# ginabt.net
KiCad netlist of a schematic drawn in EAGLE
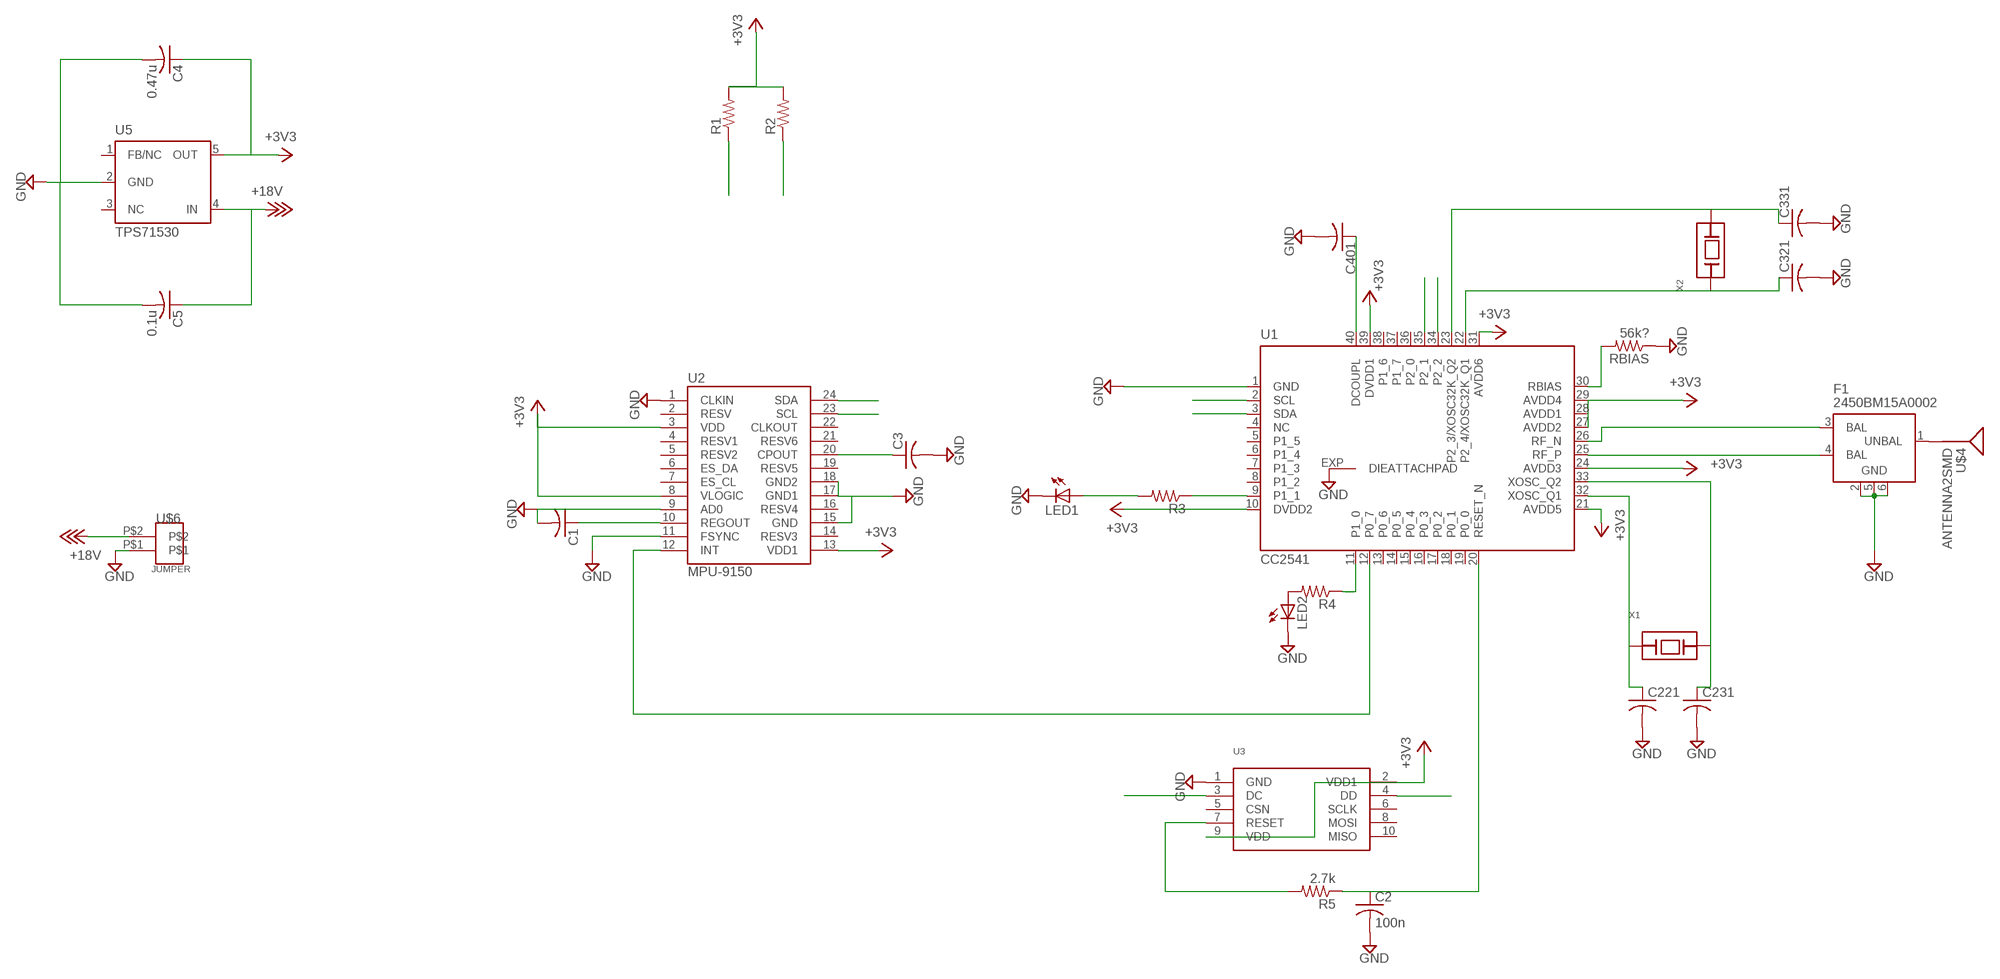
[diagram p0: schematic, sheet 1]

(export (version "E")
  (design (tool "Eeschema 10.0.6"))
  (components
    (comp (ref "C1")
      (value "C-USC0402K")
      (footprint "eagle-import:C0402K")
      (libsource (lib "eagle-import") (part "C-USC0402K"))
    )
    (comp (ref "C2")
      (value "100n")
      (footprint "eagle-import:C0402K")
      (libsource (lib "eagle-import") (part "C-USC0402K"))
    )
    (comp (ref "C3")
      (value "C-USC0402K")
      (footprint "eagle-import:C0402K")
      (libsource (lib "eagle-import") (part "C-USC0402K"))
    )
    (comp (ref "C4")
      (value "0.47u")
      (footprint "eagle-import:C0402K")
      (libsource (lib "eagle-import") (part "C-USC0402K"))
    )
    (comp (ref "C5")
      (value "0.1u")
      (footprint "eagle-import:C0402K")
      (libsource (lib "eagle-import") (part "C-USC0402K"))
    )
    (comp (ref "C221")
      (value "C-USC0402K")
      (footprint "eagle-import:C0402K")
      (libsource (lib "eagle-import") (part "C-USC0402K"))
    )
    (comp (ref "C231")
      (value "C-USC0402K")
      (footprint "eagle-import:C0402K")
      (libsource (lib "eagle-import") (part "C-USC0402K"))
    )
    (comp (ref "C321")
      (value "C-USC0402K")
      (footprint "eagle-import:C0402K")
      (libsource (lib "eagle-import") (part "C-USC0402K"))
    )
    (comp (ref "C331")
      (value "C-USC0402K")
      (footprint "eagle-import:C0402K")
      (libsource (lib "eagle-import") (part "C-USC0402K"))
    )
    (comp (ref "C401")
      (value "C-USC0402K")
      (footprint "eagle-import:C0402K")
      (libsource (lib "eagle-import") (part "C-USC0402K"))
    )
    (comp (ref "F1")
      (value "2450BM15A0002")
      (footprint "eagle-import:2450BM15A0002")
      (libsource (lib "eagle-import") (part "2450BM15A0002"))
    )
    (comp (ref "LED1")
      (value "LED")
      (footprint "eagle-import:SMARTLED-TTW")
      (libsource (lib "eagle-import") (part "LED"))
    )
    (comp (ref "LED2")
      (value "LED")
      (footprint "eagle-import:SMARTLED-TTW")
      (libsource (lib "eagle-import") (part "LED"))
    )
    (comp (ref "R1")
      (value "R-US_R0402")
      (footprint "eagle-import:R0402")
      (libsource (lib "eagle-import") (part "R-US_R0402"))
    )
    (comp (ref "R2")
      (value "R-US_R0402")
      (footprint "eagle-import:R0402")
      (libsource (lib "eagle-import") (part "R-US_R0402"))
    )
    (comp (ref "R3")
      (value "R-US_R0402")
      (footprint "eagle-import:R0402")
      (libsource (lib "eagle-import") (part "R-US_R0402"))
    )
    (comp (ref "R4")
      (value "R-US_R0402")
      (footprint "eagle-import:R0402")
      (libsource (lib "eagle-import") (part "R-US_R0402"))
    )
    (comp (ref "R5")
      (value "2.7k")
      (footprint "eagle-import:R0402")
      (libsource (lib "eagle-import") (part "R-US_R0402"))
    )
    (comp (ref "RBIAS")
      (value "56k?")
      (footprint "eagle-import:R0402")
      (libsource (lib "eagle-import") (part "R-US_R0402"))
    )
    (comp (ref "U$4")
      (value "ANTENNA2SMD")
      (footprint "eagle-import:ANTENNA-CHIP2")
      (libsource (lib "eagle-import") (part "ANTENNA2SMD"))
    )
    (comp (ref "U$6")
      (value "JUMPER")
      (footprint "eagle-import:JUMPER_1X2_80MIL")
      (libsource (lib "eagle-import") (part "JUMPER"))
    )
    (comp (ref "U1")
      (value "CC2541")
      (footprint "eagle-import:RHA_S-PVQFN-N40")
      (libsource (lib "eagle-import") (part "CC2541"))
    )
    (comp (ref "U2")
      (value "MPU-9150")
      (footprint "eagle-import:LGA-24")
      (libsource (lib "eagle-import") (part "MPU-9150"))
    )
    (comp (ref "U3")
      (value "CCDEBUGGER")
      (footprint "eagle-import:SMD-050-HEADER-2X5")
      (libsource (lib "eagle-import") (part "CCDEBUGGER"))
    )
    (comp (ref "U5")
      (value "TPS71530")
      (footprint "eagle-import:DCK_R-PDSO-G5")
      (libsource (lib "eagle-import") (part "TPS71530"))
    )
    (comp (ref "X1")
      (value "XTALABS07")
      (footprint "eagle-import:ABS07")
      (libsource (lib "eagle-import") (part "XTALABS07"))
    )
    (comp (ref "X2")
      (value "XTALCX3225SA")
      (footprint "eagle-import:CX3225SA")
      (libsource (lib "eagle-import") (part "XTALCX3225SA"))
    )
  )
  (nets
    (net (code "1") (name "+3V3") (class "Default")
      (node (ref "C4") (pin "1") (pinfunction "1_1") (pintype "passive"))
      (node (ref "R1") (pin "2") (pinfunction "2_2") (pintype "passive"))
      (node (ref "R2") (pin "2") (pinfunction "2_2") (pintype "passive"))
      (node (ref "U1") (pin "10") (pinfunction "DVDD2_10") (pintype "power_in"))
      (node (ref "U1") (pin "21") (pinfunction "AVDD5_21") (pintype "power_in"))
      (node (ref "U1") (pin "24") (pinfunction "AVDD3_24") (pintype "power_in"))
      (node (ref "U1") (pin "27") (pinfunction "AVDD2_27") (pintype "power_in"))
      (node (ref "U1") (pin "28") (pinfunction "AVDD1_28") (pintype "power_in"))
      (node (ref "U1") (pin "29") (pinfunction "AVDD4_29") (pintype "power_in"))
      (node (ref "U1") (pin "31") (pinfunction "AVDD6_31") (pintype "power_in"))
      (node (ref "U1") (pin "39") (pinfunction "DVDD1_39") (pintype "power_in"))
      (node (ref "U2") (pin "13") (pinfunction "VDD1_13") (pintype "bidirectional"))
      (node (ref "U2") (pin "3") (pinfunction "VDD_3") (pintype "power_in"))
      (node (ref "U2") (pin "8") (pinfunction "VLOGIC_8") (pintype "bidirectional"))
      (node (ref "U3") (pin "2") (pinfunction "VDD1_2") (pintype "bidirectional"))
      (node (ref "U3") (pin "9") (pinfunction "VDD_9") (pintype "bidirectional"))
      (node (ref "U5") (pin "5") (pinfunction "OUT_5") (pintype "passive"))
    )
    (net (code "2") (name "+18V") (class "Default")
      (node (ref "C5") (pin "1") (pinfunction "1_1") (pintype "passive"))
      (node (ref "U$6") (pin "P$2") (pinfunction "P$2_P$2") (pintype "bidirectional"))
      (node (ref "U5") (pin "4") (pinfunction "IN_4") (pintype "passive"))
    )
    (net (code "3") (name "/DC") (class "Default")
      (node (ref "U1") (pin "34") (pinfunction "P2_2_34") (pintype "bidirectional"))
      (node (ref "U3") (pin "3") (pinfunction "DC_3") (pintype "bidirectional"))
    )
    (net (code "4") (name "/DD") (class "Default")
      (node (ref "U1") (pin "35") (pinfunction "P2_1_35") (pintype "bidirectional"))
      (node (ref "U3") (pin "4") (pinfunction "DD_4") (pintype "bidirectional"))
    )
    (net (code "5") (name "/NC") (class "Default")
      (node (ref "U5") (pin "3") (pinfunction "NC_3") (pintype "power_in"))
    )
    (net (code "6") (name "/SCL") (class "Default")
      (node (ref "R1") (pin "1") (pinfunction "1_1") (pintype "passive"))
      (node (ref "U1") (pin "2") (pinfunction "SCL_2") (pintype "bidirectional"))
      (node (ref "U2") (pin "23") (pinfunction "SCL_23") (pintype "bidirectional"))
    )
    (net (code "7") (name "/SDA") (class "Default")
      (node (ref "R2") (pin "1") (pinfunction "1_1") (pintype "passive"))
      (node (ref "U1") (pin "3") (pinfunction "SDA_3") (pintype "bidirectional"))
      (node (ref "U2") (pin "24") (pinfunction "SDA_24") (pintype "bidirectional"))
    )
    (net (code "8") (name "GND") (class "Default")
      (node (ref "C1") (pin "2") (pinfunction "2_2") (pintype "passive"))
      (node (ref "C2") (pin "2") (pinfunction "2_2") (pintype "passive"))
      (node (ref "C221") (pin "2") (pinfunction "2_2") (pintype "passive"))
      (node (ref "C231") (pin "2") (pinfunction "2_2") (pintype "passive"))
      (node (ref "C3") (pin "2") (pinfunction "2_2") (pintype "passive"))
      (node (ref "C321") (pin "2") (pinfunction "2_2") (pintype "passive"))
      (node (ref "C331") (pin "2") (pinfunction "2_2") (pintype "passive"))
      (node (ref "C4") (pin "2") (pinfunction "2_2") (pintype "passive"))
      (node (ref "C401") (pin "2") (pinfunction "2_2") (pintype "passive"))
      (node (ref "C5") (pin "2") (pinfunction "2_2") (pintype "passive"))
      (node (ref "F1") (pin "2") (pinfunction "GND_2") (pintype "passive"))
      (node (ref "F1") (pin "5") (pinfunction "GND_5") (pintype "passive"))
      (node (ref "F1") (pin "6") (pinfunction "GND_6") (pintype "passive"))
      (node (ref "LED1") (pin "C@1") (pinfunction "C_C@1") (pintype "passive"))
      (node (ref "LED2") (pin "C@1") (pinfunction "C_C@1") (pintype "passive"))
      (node (ref "RBIAS") (pin "1") (pinfunction "1_1") (pintype "passive"))
      (node (ref "U$6") (pin "P$1") (pinfunction "P$1_P$1") (pintype "bidirectional"))
      (node (ref "U1") (pin "1") (pinfunction "GND_1") (pintype "power_in"))
      (node (ref "U1") (pin "EXP") (pinfunction "DIEATTACHPAD_EXP") (pintype "power_in"))
      (node (ref "U2") (pin "1") (pinfunction "CLKIN_1") (pintype "bidirectional"))
      (node (ref "U2") (pin "11") (pinfunction "FSYNC_11") (pintype "bidirectional"))
      (node (ref "U2") (pin "15") (pinfunction "GND_15") (pintype "power_in"))
      (node (ref "U2") (pin "17") (pinfunction "GND1_17") (pintype "power_in"))
      (node (ref "U2") (pin "18") (pinfunction "GND2_18") (pintype "power_in"))
      (node (ref "U2") (pin "9") (pinfunction "AD0_9") (pintype "bidirectional"))
      (node (ref "U3") (pin "1") (pinfunction "GND_1") (pintype "bidirectional"))
      (node (ref "U5") (pin "2") (pinfunction "GND_2") (pintype "input"))
    )
    (net (code "9") (name "Net-(F1-UNBAL)") (class "Default")
      (node (ref "F1") (pin "1") (pinfunction "UNBAL_1") (pintype "passive"))
      (node (ref "U$4") (pin "FEED") (pinfunction "SIGNAL_FEED") (pintype "bidirectional"))
    )
    (net (code "10") (name "Net-(LED1-A)") (class "Default")
      (node (ref "LED1") (pin "A@1") (pinfunction "A_A@1") (pintype "passive"))
      (node (ref "R3") (pin "2") (pinfunction "2_2") (pintype "passive"))
    )
    (net (code "11") (name "Net-(LED2-A)") (class "Default")
      (node (ref "LED2") (pin "A@1") (pinfunction "A_A@1") (pintype "passive"))
      (node (ref "R4") (pin "2") (pinfunction "2_2") (pintype "passive"))
    )
    (net (code "12") (name "Net-(U1-DCOUPL)") (class "Default")
      (node (ref "C401") (pin "1") (pinfunction "1_1") (pintype "passive"))
      (node (ref "U1") (pin "40") (pinfunction "DCOUPL_40") (pintype "power_in"))
    )
    (net (code "13") (name "Net-(U1-P0_7)") (class "Default")
      (node (ref "U1") (pin "12") (pinfunction "P0_7_12") (pintype "bidirectional"))
      (node (ref "U2") (pin "12") (pinfunction "INT_12") (pintype "bidirectional"))
    )
    (net (code "14") (name "Net-(U1-P1_0)") (class "Default")
      (node (ref "R4") (pin "1") (pinfunction "1_1") (pintype "passive"))
      (node (ref "U1") (pin "11") (pinfunction "P1_0_11") (pintype "bidirectional"))
    )
    (net (code "15") (name "Net-(U1-P1_1)") (class "Default")
      (node (ref "R3") (pin "1") (pinfunction "1_1") (pintype "passive"))
      (node (ref "U1") (pin "9") (pinfunction "P1_1_9") (pintype "bidirectional"))
    )
    (net (code "16") (name "Net-(U1-P2_3{slash}XOSC32K_Q2)") (class "Default")
      (node (ref "C331") (pin "1") (pinfunction "1_1") (pintype "passive"))
      (node (ref "U1") (pin "23") (pinfunction "P2_3/XOSC32K_Q2_23") (pintype "bidirectional"))
      (node (ref "X2") (pin "1") (pinfunction "B_1") (pintype "bidirectional"))
    )
    (net (code "17") (name "Net-(U1-P2_4{slash}XOSC32K_Q1)") (class "Default")
      (node (ref "C321") (pin "1") (pinfunction "1_1") (pintype "passive"))
      (node (ref "U1") (pin "22") (pinfunction "P2_4/XOSC32K_Q1_22") (pintype "bidirectional"))
      (node (ref "X2") (pin "3") (pinfunction "A_3") (pintype "bidirectional"))
    )
    (net (code "18") (name "Net-(U1-RBIAS)") (class "Default")
      (node (ref "RBIAS") (pin "2") (pinfunction "2_2") (pintype "passive"))
      (node (ref "U1") (pin "30") (pinfunction "RBIAS_30") (pintype "bidirectional"))
    )
    (net (code "19") (name "Net-(U1-RESET_N)") (class "Default")
      (node (ref "C2") (pin "1") (pinfunction "1_1") (pintype "passive"))
      (node (ref "R5") (pin "1") (pinfunction "1_1") (pintype "passive"))
      (node (ref "U1") (pin "20") (pinfunction "RESET_N_20") (pintype "input"))
    )
    (net (code "20") (name "Net-(U1-RF_N)") (class "Default")
      (node (ref "F1") (pin "3") (pinfunction "BAL_3") (pintype "passive"))
      (node (ref "U1") (pin "26") (pinfunction "RF_N_26") (pintype "input"))
    )
    (net (code "21") (name "Net-(U1-RF_P)") (class "Default")
      (node (ref "F1") (pin "4") (pinfunction "BAL_4") (pintype "passive"))
      (node (ref "U1") (pin "25") (pinfunction "RF_P_25") (pintype "input"))
    )
    (net (code "22") (name "Net-(U1-XOSC_Q1)") (class "Default")
      (node (ref "C221") (pin "1") (pinfunction "1_1") (pintype "passive"))
      (node (ref "U1") (pin "32") (pinfunction "XOSC_Q1_32") (pintype "bidirectional"))
      (node (ref "X1") (pin "1") (pinfunction "A_1") (pintype "bidirectional"))
    )
    (net (code "23") (name "Net-(U1-XOSC_Q2)") (class "Default")
      (node (ref "C231") (pin "1") (pinfunction "1_1") (pintype "passive"))
      (node (ref "U1") (pin "33") (pinfunction "XOSC_Q2_33") (pintype "bidirectional"))
      (node (ref "X1") (pin "2") (pinfunction "B_2") (pintype "bidirectional"))
    )
    (net (code "24") (name "Net-(U2-CPOUT)") (class "Default")
      (node (ref "C3") (pin "1") (pinfunction "1_1") (pintype "passive"))
      (node (ref "U2") (pin "20") (pinfunction "CPOUT_20") (pintype "bidirectional"))
    )
    (net (code "25") (name "Net-(U2-REGOUT)") (class "Default")
      (node (ref "C1") (pin "1") (pinfunction "1_1") (pintype "passive"))
      (node (ref "U2") (pin "10") (pinfunction "REGOUT_10") (pintype "bidirectional"))
    )
    (net (code "26") (name "Net-(U3-RESET)") (class "Default")
      (node (ref "R5") (pin "2") (pinfunction "2_2") (pintype "passive"))
      (node (ref "U3") (pin "7") (pinfunction "RESET_7") (pintype "bidirectional"))
    )
    (net (code "27") (name "unconnected-(U1-NC-Pad4)") (class "Default")
      (node (ref "U1") (pin "4") (pinfunction "NC_4") (pintype "no_connect"))
    )
    (net (code "28") (name "unconnected-(U1-P0_0-Pad19)") (class "Default")
      (node (ref "U1") (pin "19") (pinfunction "P0_0_19") (pintype "bidirectional"))
    )
    (net (code "29") (name "unconnected-(U1-P0_1-Pad18)") (class "Default")
      (node (ref "U1") (pin "18") (pinfunction "P0_1_18") (pintype "bidirectional"))
    )
    (net (code "30") (name "unconnected-(U1-P0_2-Pad17)") (class "Default")
      (node (ref "U1") (pin "17") (pinfunction "P0_2_17") (pintype "bidirectional"))
    )
    (net (code "31") (name "unconnected-(U1-P0_3-Pad16)") (class "Default")
      (node (ref "U1") (pin "16") (pinfunction "P0_3_16") (pintype "bidirectional"))
    )
    (net (code "32") (name "unconnected-(U1-P0_4-Pad15)") (class "Default")
      (node (ref "U1") (pin "15") (pinfunction "P0_4_15") (pintype "bidirectional"))
    )
    (net (code "33") (name "unconnected-(U1-P0_5-Pad14)") (class "Default")
      (node (ref "U1") (pin "14") (pinfunction "P0_5_14") (pintype "bidirectional"))
    )
    (net (code "34") (name "unconnected-(U1-P0_6-Pad13)") (class "Default")
      (node (ref "U1") (pin "13") (pinfunction "P0_6_13") (pintype "bidirectional"))
    )
    (net (code "35") (name "unconnected-(U1-P1_2-Pad8)") (class "Default")
      (node (ref "U1") (pin "8") (pinfunction "P1_2_8") (pintype "bidirectional"))
    )
    (net (code "36") (name "unconnected-(U1-P1_3-Pad7)") (class "Default")
      (node (ref "U1") (pin "7") (pinfunction "P1_3_7") (pintype "bidirectional"))
    )
    (net (code "37") (name "unconnected-(U1-P1_4-Pad6)") (class "Default")
      (node (ref "U1") (pin "6") (pinfunction "P1_4_6") (pintype "bidirectional"))
    )
    (net (code "38") (name "unconnected-(U1-P1_5-Pad5)") (class "Default")
      (node (ref "U1") (pin "5") (pinfunction "P1_5_5") (pintype "bidirectional"))
    )
    (net (code "39") (name "unconnected-(U1-P1_6-Pad38)") (class "Default")
      (node (ref "U1") (pin "38") (pinfunction "P1_6_38") (pintype "bidirectional"))
    )
    (net (code "40") (name "unconnected-(U1-P1_7-Pad37)") (class "Default")
      (node (ref "U1") (pin "37") (pinfunction "P1_7_37") (pintype "bidirectional"))
    )
    (net (code "41") (name "unconnected-(U1-P2_0-Pad36)") (class "Default")
      (node (ref "U1") (pin "36") (pinfunction "P2_0_36") (pintype "bidirectional"))
    )
    (net (code "42") (name "unconnected-(U2-CLKOUT-Pad22)") (class "Default")
      (node (ref "U2") (pin "22") (pinfunction "CLKOUT_22") (pintype "bidirectional"))
    )
    (net (code "43") (name "unconnected-(U2-ES_CL-Pad7)") (class "Default")
      (node (ref "U2") (pin "7") (pinfunction "ES_CL_7") (pintype "bidirectional"))
    )
    (net (code "44") (name "unconnected-(U2-ES_DA-Pad6)") (class "Default")
      (node (ref "U2") (pin "6") (pinfunction "ES_DA_6") (pintype "bidirectional"))
    )
    (net (code "45") (name "unconnected-(U2-RESV-Pad2)") (class "Default")
      (node (ref "U2") (pin "2") (pinfunction "RESV_2") (pintype "no_connect"))
    )
    (net (code "46") (name "unconnected-(U2-RESV1-Pad4)") (class "Default")
      (node (ref "U2") (pin "4") (pinfunction "RESV1_4") (pintype "no_connect"))
    )
    (net (code "47") (name "unconnected-(U2-RESV2-Pad5)") (class "Default")
      (node (ref "U2") (pin "5") (pinfunction "RESV2_5") (pintype "no_connect"))
    )
    (net (code "48") (name "unconnected-(U2-RESV3-Pad14)") (class "Default")
      (node (ref "U2") (pin "14") (pinfunction "RESV3_14") (pintype "no_connect"))
    )
    (net (code "49") (name "unconnected-(U2-RESV4-Pad16)") (class "Default")
      (node (ref "U2") (pin "16") (pinfunction "RESV4_16") (pintype "no_connect"))
    )
    (net (code "50") (name "unconnected-(U2-RESV5-Pad19)") (class "Default")
      (node (ref "U2") (pin "19") (pinfunction "RESV5_19") (pintype "no_connect"))
    )
    (net (code "51") (name "unconnected-(U2-RESV6-Pad21)") (class "Default")
      (node (ref "U2") (pin "21") (pinfunction "RESV6_21") (pintype "no_connect"))
    )
    (net (code "52") (name "unconnected-(U3-CSN-Pad5)") (class "Default")
      (node (ref "U3") (pin "5") (pinfunction "CSN_5") (pintype "bidirectional"))
    )
    (net (code "53") (name "unconnected-(U3-MISO-Pad10)") (class "Default")
      (node (ref "U3") (pin "10") (pinfunction "MISO_10") (pintype "bidirectional"))
    )
    (net (code "54") (name "unconnected-(U3-MOSI-Pad8)") (class "Default")
      (node (ref "U3") (pin "8") (pinfunction "MOSI_8") (pintype "bidirectional"))
    )
    (net (code "55") (name "unconnected-(U3-SCLK-Pad6)") (class "Default")
      (node (ref "U3") (pin "6") (pinfunction "SCLK_6") (pintype "bidirectional"))
    )
    (net (code "56") (name "unconnected-(U5-FB{slash}NC-Pad1)") (class "Default")
      (node (ref "U5") (pin "1") (pinfunction "FB/NC_1") (pintype "input"))
    )
  )
)
